# CE_BJTInfineonSOT343_Simple_v1.net
KiCad netlist of a schematic drawn in Altium Designer
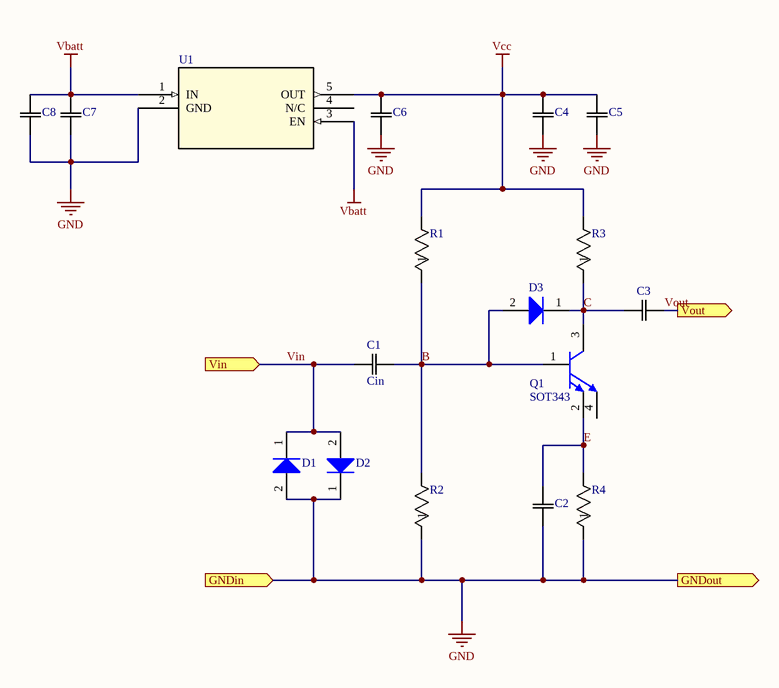
[diagram p0: CE_BJTInfineonSOT343_Simple_v1.SchDoc]

(export (version "E")
  (design (tool "Eeschema 10.0.6"))
  (components
    (comp (ref "C1")
      (value "Cin")
      (footprint "C0201")
      (description "No Description Available")
      (fields
        (field (name "MANUFACTURER_PART_NUMBER") "C0201C270J3GACTU")
        (field (name "COPYRIGHT") "Copyright (C) 2018 Accelerated Designs. All rights reserved")
      )
      (libsource (lib "0201Capacitor_Yageo") (part "C0201C270J3GACTU"))
    )
    (comp (ref "C2")
      (value "~")
      (footprint "C0201")
      (description "No Description Available")
      (fields
        (field (name "MANUFACTURER_PART_NUMBER") "C0201C270J3GACTU")
        (field (name "COPYRIGHT") "Copyright (C) 2018 Accelerated Designs. All rights reserved")
      )
      (libsource (lib "0201Capacitor_Yageo") (part "C0201C270J3GACTU"))
    )
    (comp (ref "C3")
      (value "~")
      (footprint "C0201")
      (description "No Description Available")
      (fields
        (field (name "MANUFACTURER_PART_NUMBER") "C0201C270J3GACTU")
        (field (name "COPYRIGHT") "Copyright (C) 2018 Accelerated Designs. All rights reserved")
      )
      (libsource (lib "0201Capacitor_Yageo") (part "C0201C270J3GACTU"))
    )
    (comp (ref "C4")
      (value "~")
      (footprint "CAP_CBR_0201")
      (description "No Description Available")
      (fields
        (field (name "MANUFACTURER_PART_NUMBER") "CBR02C399C3GAC")
        (field (name "COPYRIGHT") "Copyright (C) 2018 Accelerated Designs. All rights reserved")
      )
      (libsource (lib "0201Capacitor_KEMET") (part "CBR02C399C3GAC"))
    )
    (comp (ref "C5")
      (value "~")
      (footprint "CAP_CBR_0201")
      (description "No Description Available")
      (fields
        (field (name "MANUFACTURER_PART_NUMBER") "CBR02C399C3GAC")
        (field (name "COPYRIGHT") "Copyright (C) 2018 Accelerated Designs. All rights reserved")
      )
      (libsource (lib "0201Capacitor_KEMET") (part "CBR02C399C3GAC"))
    )
    (comp (ref "C6")
      (value "~")
      (footprint "YAG_CC0402")
      (description "No Description Available")
      (fields
        (field (name "MANUFACTURER_PART_NUMBER") "CC0402KRX7R9BB103")
        (field (name "COPYRIGHT") "Copyright (C) 2018 Accelerated Designs. All rights reserved")
      )
      (libsource (lib "0402Capacitor_Yageo") (part "CC0402KRX7R9BB10"))
    )
    (comp (ref "C7")
      (value "~")
      (footprint "YAG_CC0402")
      (description "No Description Available")
      (fields
        (field (name "MANUFACTURER_PART_NUMBER") "CC0402KRX7R9BB103")
        (field (name "COPYRIGHT") "Copyright (C) 2018 Accelerated Designs. All rights reserved")
      )
      (libsource (lib "0402Capacitor_Yageo") (part "CC0402KRX7R9BB10"))
    )
    (comp (ref "C8")
      (value "~")
      (footprint "YAG_CC0402")
      (description "No Description Available")
      (fields
        (field (name "MANUFACTURER_PART_NUMBER") "CC0402KRX7R9BB103")
        (field (name "COPYRIGHT") "Copyright (C) 2018 Accelerated Designs. All rights reserved")
      )
      (libsource (lib "0402Capacitor_Yageo") (part "CC0402KRX7R9BB10"))
    )
    (comp (ref "D1")
      (value "~")
      (footprint "INF-SOD323_V")
      (description "Single Silicon Schottky Diode, 110 mA IF Max, SOD32, Green")
      (fields (field (name "MANUFACTURER") "Infineon") (field (name "PARTNUMBER") "BAT15-03W"))
      (libsource (lib "Infineon_RFSchottkyDiode_SOD323") (part "BAT15-03W"))
    )
    (comp (ref "D2")
      (value "~")
      (footprint "INF-SOD323_V")
      (description "Single Silicon Schottky Diode, 110 mA IF Max, SOD32, Green")
      (fields (field (name "MANUFACTURER") "Infineon") (field (name "PARTNUMBER") "BAT15-03W"))
      (libsource (lib "Infineon_RFSchottkyDiode_SOD323") (part "BAT15-03W"))
    )
    (comp (ref "D3")
      (value "~")
      (footprint "INF-SOD323_V")
      (description "Single Silicon Schottky Diode, 110 mA IF Max, SOD32, Green")
      (fields (field (name "MANUFACTURER") "Infineon") (field (name "PARTNUMBER") "BAT15-03W"))
      (libsource (lib "Infineon_RFSchottkyDiode_SOD323") (part "BAT15-03W"))
    )
    (comp (ref "Q1")
      (value "SOT343")
      (footprint "INF-SOT343_V")
      (fields (field (name "MANUFACTURER") "Infineon") (field (name "PARTNUMBER") "BFP840ESD"))
      (libsource (lib "Infineon_RFBJT_SOT343") (part "BFP840ESD"))
    )
    (comp (ref "R1")
      (value "~")
      (footprint "RES_RC0201_P6XP3")
      (description "No Description Available")
      (fields
        (field (name "MANUFACTURER_PART_NUMBER") "RC0201FR-0718KL")
        (field (name "COPYRIGHT") "Copyright (C) 2018 Accelerated Designs. All rights reserved")
      )
      (libsource (lib "0201Resistor_Yageo") (part "RC0201FR-0718KL"))
    )
    (comp (ref "R2")
      (value "~")
      (footprint "RES_RC0201_P6XP3")
      (description "No Description Available")
      (fields
        (field (name "MANUFACTURER_PART_NUMBER") "RC0201FR-0718KL")
        (field (name "COPYRIGHT") "Copyright (C) 2018 Accelerated Designs. All rights reserved")
      )
      (libsource (lib "0201Resistor_Yageo") (part "RC0201FR-0718KL"))
    )
    (comp (ref "R3")
      (value "~")
      (footprint "RES_RC0201_P6XP3")
      (description "No Description Available")
      (fields
        (field (name "MANUFACTURER_PART_NUMBER") "RC0201FR-0718KL")
        (field (name "COPYRIGHT") "Copyright (C) 2018 Accelerated Designs. All rights reserved")
      )
      (libsource (lib "0201Resistor_Yageo") (part "RC0201FR-0718KL"))
    )
    (comp (ref "R4")
      (value "~")
      (footprint "RES_RC0201_P6XP3")
      (description "No Description Available")
      (fields
        (field (name "MANUFACTURER_PART_NUMBER") "RC0201FR-0718KL")
        (field (name "COPYRIGHT") "Copyright (C) 2018 Accelerated Designs. All rights reserved")
      )
      (libsource (lib "0201Resistor_Yageo") (part "RC0201FR-0718KL"))
    )
    (comp (ref "U1")
      (value "~")
      (footprint "DBV5")
      (description "No Description Available")
      (fields
        (field (name "MANUFACTURER_PART_NUMBER") "LP5907MFX-3.3/NOPB")
        (field (name "COPYRIGHT") "Copyright (C) 2018 Accelerated Designs. All rights reserved")
      )
      (libsource (lib "TI_LDO_3V3_SOT325") (part "LP5907MFX-3.3/NO"))
    )
  )
  (nets
    (net (code "1") (name "/B") (class "Default")
      (node (ref "C1") (pin "2") (pinfunction "2_2") (pintype "passive"))
      (node (ref "D3") (pin "2") (pinfunction "A_2") (pintype "passive"))
      (node (ref "Q1") (pin "1") (pinfunction "B_1") (pintype "passive"))
      (node (ref "R1") (pin "1") (pinfunction "1_1") (pintype "passive"))
      (node (ref "R2") (pin "2") (pinfunction "2_2") (pintype "passive"))
    )
    (net (code "2") (name "/C") (class "Default")
      (node (ref "C3") (pin "1") (pinfunction "1_1") (pintype "passive"))
      (node (ref "D3") (pin "1") (pinfunction "K_1") (pintype "passive"))
      (node (ref "Q1") (pin "3") (pinfunction "C_3") (pintype "passive"))
      (node (ref "R3") (pin "1") (pinfunction "1_1") (pintype "passive"))
    )
    (net (code "3") (name "/E") (class "Default")
      (node (ref "C2") (pin "2") (pinfunction "2_2") (pintype "passive"))
      (node (ref "Q1") (pin "2") (pinfunction "E_2") (pintype "passive"))
      (node (ref "R4") (pin "2") (pinfunction "2_2") (pintype "passive"))
    )
    (net (code "4") (name "/Vin") (class "Default")
      (node (ref "C1") (pin "1") (pinfunction "1_1") (pintype "passive"))
      (node (ref "D1") (pin "1") (pinfunction "K_1") (pintype "passive"))
      (node (ref "D2") (pin "2") (pinfunction "A_2") (pintype "passive"))
    )
    (net (code "5") (name "/Vout") (class "Default")
      (node (ref "C3") (pin "2") (pinfunction "2_2") (pintype "passive"))
    )
    (net (code "6") (name "GND") (class "Default")
      (node (ref "C2") (pin "1") (pinfunction "1_1") (pintype "passive"))
      (node (ref "C4") (pin "1") (pinfunction "1_1") (pintype "passive"))
      (node (ref "C5") (pin "1") (pinfunction "1_1") (pintype "passive"))
      (node (ref "C6") (pin "1") (pinfunction "1_1") (pintype "passive"))
      (node (ref "C7") (pin "1") (pinfunction "1_1") (pintype "passive"))
      (node (ref "C8") (pin "1") (pinfunction "1_1") (pintype "passive"))
      (node (ref "D1") (pin "2") (pinfunction "A_2") (pintype "passive"))
      (node (ref "D2") (pin "1") (pinfunction "K_1") (pintype "passive"))
      (node (ref "R2") (pin "1") (pinfunction "1_1") (pintype "passive"))
      (node (ref "R4") (pin "1") (pinfunction "1_1") (pintype "passive"))
      (node (ref "U1") (pin "2") (pinfunction "GND_2") (pintype "power_in"))
    )
    (net (code "7") (name "Vbatt") (class "Default")
      (node (ref "C7") (pin "2") (pinfunction "2_2") (pintype "passive"))
      (node (ref "C8") (pin "2") (pinfunction "2_2") (pintype "passive"))
      (node (ref "U1") (pin "1") (pinfunction "IN_1") (pintype "input"))
      (node (ref "U1") (pin "3") (pinfunction "EN_3") (pintype "input"))
    )
    (net (code "8") (name "Vcc") (class "Default")
      (node (ref "C4") (pin "2") (pinfunction "2_2") (pintype "passive"))
      (node (ref "C5") (pin "2") (pinfunction "2_2") (pintype "passive"))
      (node (ref "C6") (pin "2") (pinfunction "2_2") (pintype "passive"))
      (node (ref "R1") (pin "2") (pinfunction "2_2") (pintype "passive"))
      (node (ref "R3") (pin "2") (pinfunction "2_2") (pintype "passive"))
      (node (ref "U1") (pin "5") (pinfunction "OUT_5") (pintype "output"))
    )
    (net (code "9") (name "unconnected-(Q1-E-Pad4)") (class "Default")
      (node (ref "Q1") (pin "4") (pinfunction "E_4") (pintype "passive"))
    )
    (net (code "10") (name "unconnected-(U1-N{slash}C-Pad4)") (class "Default")
      (node (ref "U1") (pin "4") (pinfunction "N/C_4") (pintype "passive"))
    )
  )
)
